# bckpln.net
KiCad netlist of a schematic drawn in Altium Designer
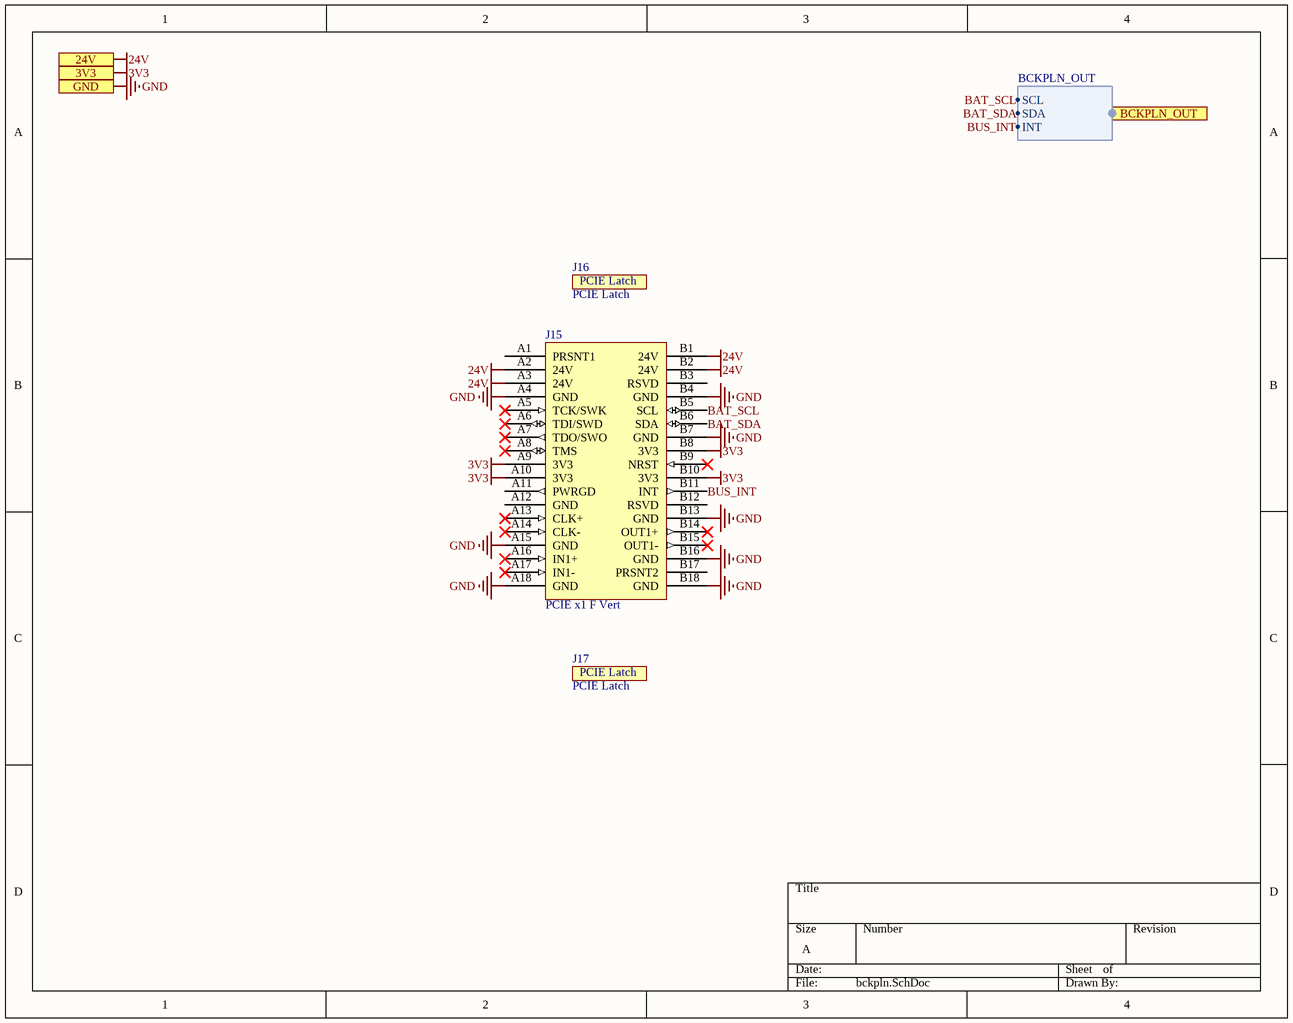
[diagram p0: bckpln.SchDoc]

(export (version "E")
  (design (tool "Eeschema 10.0.6"))
  (components
    (comp (ref "J15")
      (value "PCIE x1 F Vert")
      (footprint "CONN PCIE x1 F Vert")
      (description "10018784-10210TLF")
      (libsource (lib "streetbot") (part "CONN PCIE x1 F Vert"))
    )
    (comp (ref "J16")
      (value "PCIE Latch")
      (footprint "CONN PCIE F Latch")
      (description "CONN ACCY CARD RETENTION BLACK")
      (libsource (lib "streetbot") (part "CONN PCIE F Latch"))
    )
    (comp (ref "J17")
      (value "PCIE Latch")
      (footprint "CONN PCIE F Latch")
      (description "CONN ACCY CARD RETENTION BLACK")
      (libsource (lib "streetbot") (part "CONN PCIE F Latch"))
    )
  )
  (nets
    (net (code "2") (name "/BAT_SCL") (class "Default")
      (node (ref "J15") (pin "B5") (pinfunction "SCL_B5") (pintype "bidirectional"))
    )
    (net (code "3") (name "/BAT_SDA") (class "Default")
      (node (ref "J15") (pin "B6") (pinfunction "SDA_B6") (pintype "bidirectional"))
    )
    (net (code "4") (name "/BUS_INT") (class "Default")
      (node (ref "J15") (pin "B11") (pinfunction "INT_B11") (pintype "output"))
    )
    (net (code "6") (name "3V3") (class "Default")
      (node (ref "J15") (pin "A10") (pinfunction "3V3_A10") (pintype "power_in"))
      (node (ref "J15") (pin "A9") (pinfunction "3V3_A9") (pintype "power_in"))
      (node (ref "J15") (pin "B10") (pinfunction "3V3_B10") (pintype "power_in"))
      (node (ref "J15") (pin "B8") (pinfunction "3V3_B8") (pintype "power_in"))
    )
    (net (code "7") (name "24V") (class "Default")
      (node (ref "J15") (pin "A2") (pinfunction "24V_A2") (pintype "power_in"))
      (node (ref "J15") (pin "A3") (pinfunction "24V_A3") (pintype "power_in"))
      (node (ref "J15") (pin "B1") (pinfunction "24V_B1") (pintype "power_in"))
      (node (ref "J15") (pin "B2") (pinfunction "24V_B2") (pintype "power_in"))
    )
    (net (code "8") (name "GND") (class "Default")
      (node (ref "J15") (pin "A15") (pinfunction "GND_A15") (pintype "power_in"))
      (node (ref "J15") (pin "A18") (pinfunction "GND_A18") (pintype "power_in"))
      (node (ref "J15") (pin "A4") (pinfunction "GND_A4") (pintype "power_in"))
      (node (ref "J15") (pin "B13") (pinfunction "GND_B13") (pintype "power_in"))
      (node (ref "J15") (pin "B16") (pinfunction "GND_B16") (pintype "power_in"))
      (node (ref "J15") (pin "B18") (pinfunction "GND_B18") (pintype "power_in"))
      (node (ref "J15") (pin "B4") (pinfunction "GND_B4") (pintype "power_in"))
      (node (ref "J15") (pin "B7") (pinfunction "GND_B7") (pintype "power_in"))
    )
    (net (code "9") (name "unconnected-(J15-CLK+-PadA13)") (class "Default")
      (node (ref "J15") (pin "A13") (pinfunction "CLK+_A13") (pintype "input+no_connect"))
    )
    (net (code "10") (name "unconnected-(J15-CLK--PadA14)") (class "Default")
      (node (ref "J15") (pin "A14") (pinfunction "CLK-_A14") (pintype "input+no_connect"))
    )
    (net (code "11") (name "unconnected-(J15-GND-PadA12)") (class "Default")
      (node (ref "J15") (pin "A12") (pinfunction "GND_A12") (pintype "power_in"))
    )
    (net (code "12") (name "unconnected-(J15-IN1+-PadA16)") (class "Default")
      (node (ref "J15") (pin "A16") (pinfunction "IN1+_A16") (pintype "input+no_connect"))
    )
    (net (code "13") (name "unconnected-(J15-IN1--PadA17)") (class "Default")
      (node (ref "J15") (pin "A17") (pinfunction "IN1-_A17") (pintype "input+no_connect"))
    )
    (net (code "14") (name "unconnected-(J15-NRST-PadB9)") (class "Default")
      (node (ref "J15") (pin "B9") (pinfunction "NRST_B9") (pintype "input+no_connect"))
    )
    (net (code "15") (name "unconnected-(J15-OUT1+-PadB14)") (class "Default")
      (node (ref "J15") (pin "B14") (pinfunction "OUT1+_B14") (pintype "output+no_connect"))
    )
    (net (code "16") (name "unconnected-(J15-OUT1--PadB15)") (class "Default")
      (node (ref "J15") (pin "B15") (pinfunction "OUT1-_B15") (pintype "output+no_connect"))
    )
    (net (code "17") (name "unconnected-(J15-PRSNT1-PadA1)") (class "Default")
      (node (ref "J15") (pin "A1") (pinfunction "PRSNT1_A1") (pintype "passive"))
    )
    (net (code "18") (name "unconnected-(J15-PRSNT2-PadB17)") (class "Default")
      (node (ref "J15") (pin "B17") (pinfunction "PRSNT2_B17") (pintype "passive"))
    )
    (net (code "19") (name "unconnected-(J15-PWRGD-PadA11)") (class "Default")
      (node (ref "J15") (pin "A11") (pinfunction "PWRGD_A11") (pintype "output"))
    )
    (net (code "20") (name "unconnected-(J15-RSVD-PadB3)") (class "Default")
      (node (ref "J15") (pin "B3") (pinfunction "RSVD_B3") (pintype "passive"))
    )
    (net (code "21") (name "unconnected-(J15-RSVD-PadB12)") (class "Default")
      (node (ref "J15") (pin "B12") (pinfunction "RSVD_B12") (pintype "passive"))
    )
    (net (code "22") (name "unconnected-(J15-TCK{slash}SWK-PadA5)") (class "Default")
      (node (ref "J15") (pin "A5") (pinfunction "TCK/SWK_A5") (pintype "input+no_connect"))
    )
    (net (code "23") (name "unconnected-(J15-TDI{slash}SWD-PadA6)") (class "Default")
      (node (ref "J15") (pin "A6") (pinfunction "TDI/SWD_A6") (pintype "bidirectional+no_connect"))
    )
    (net (code "24") (name "unconnected-(J15-TDO{slash}SWO-PadA7)") (class "Default")
      (node (ref "J15") (pin "A7") (pinfunction "TDO/SWO_A7") (pintype "output+no_connect"))
    )
    (net (code "25") (name "unconnected-(J15-TMS-PadA8)") (class "Default")
      (node (ref "J15") (pin "A8") (pinfunction "TMS_A8") (pintype "bidirectional+no_connect"))
    )
  )
)
